# mk.net
KiCad netlist of a schematic drawn in Altium Designer
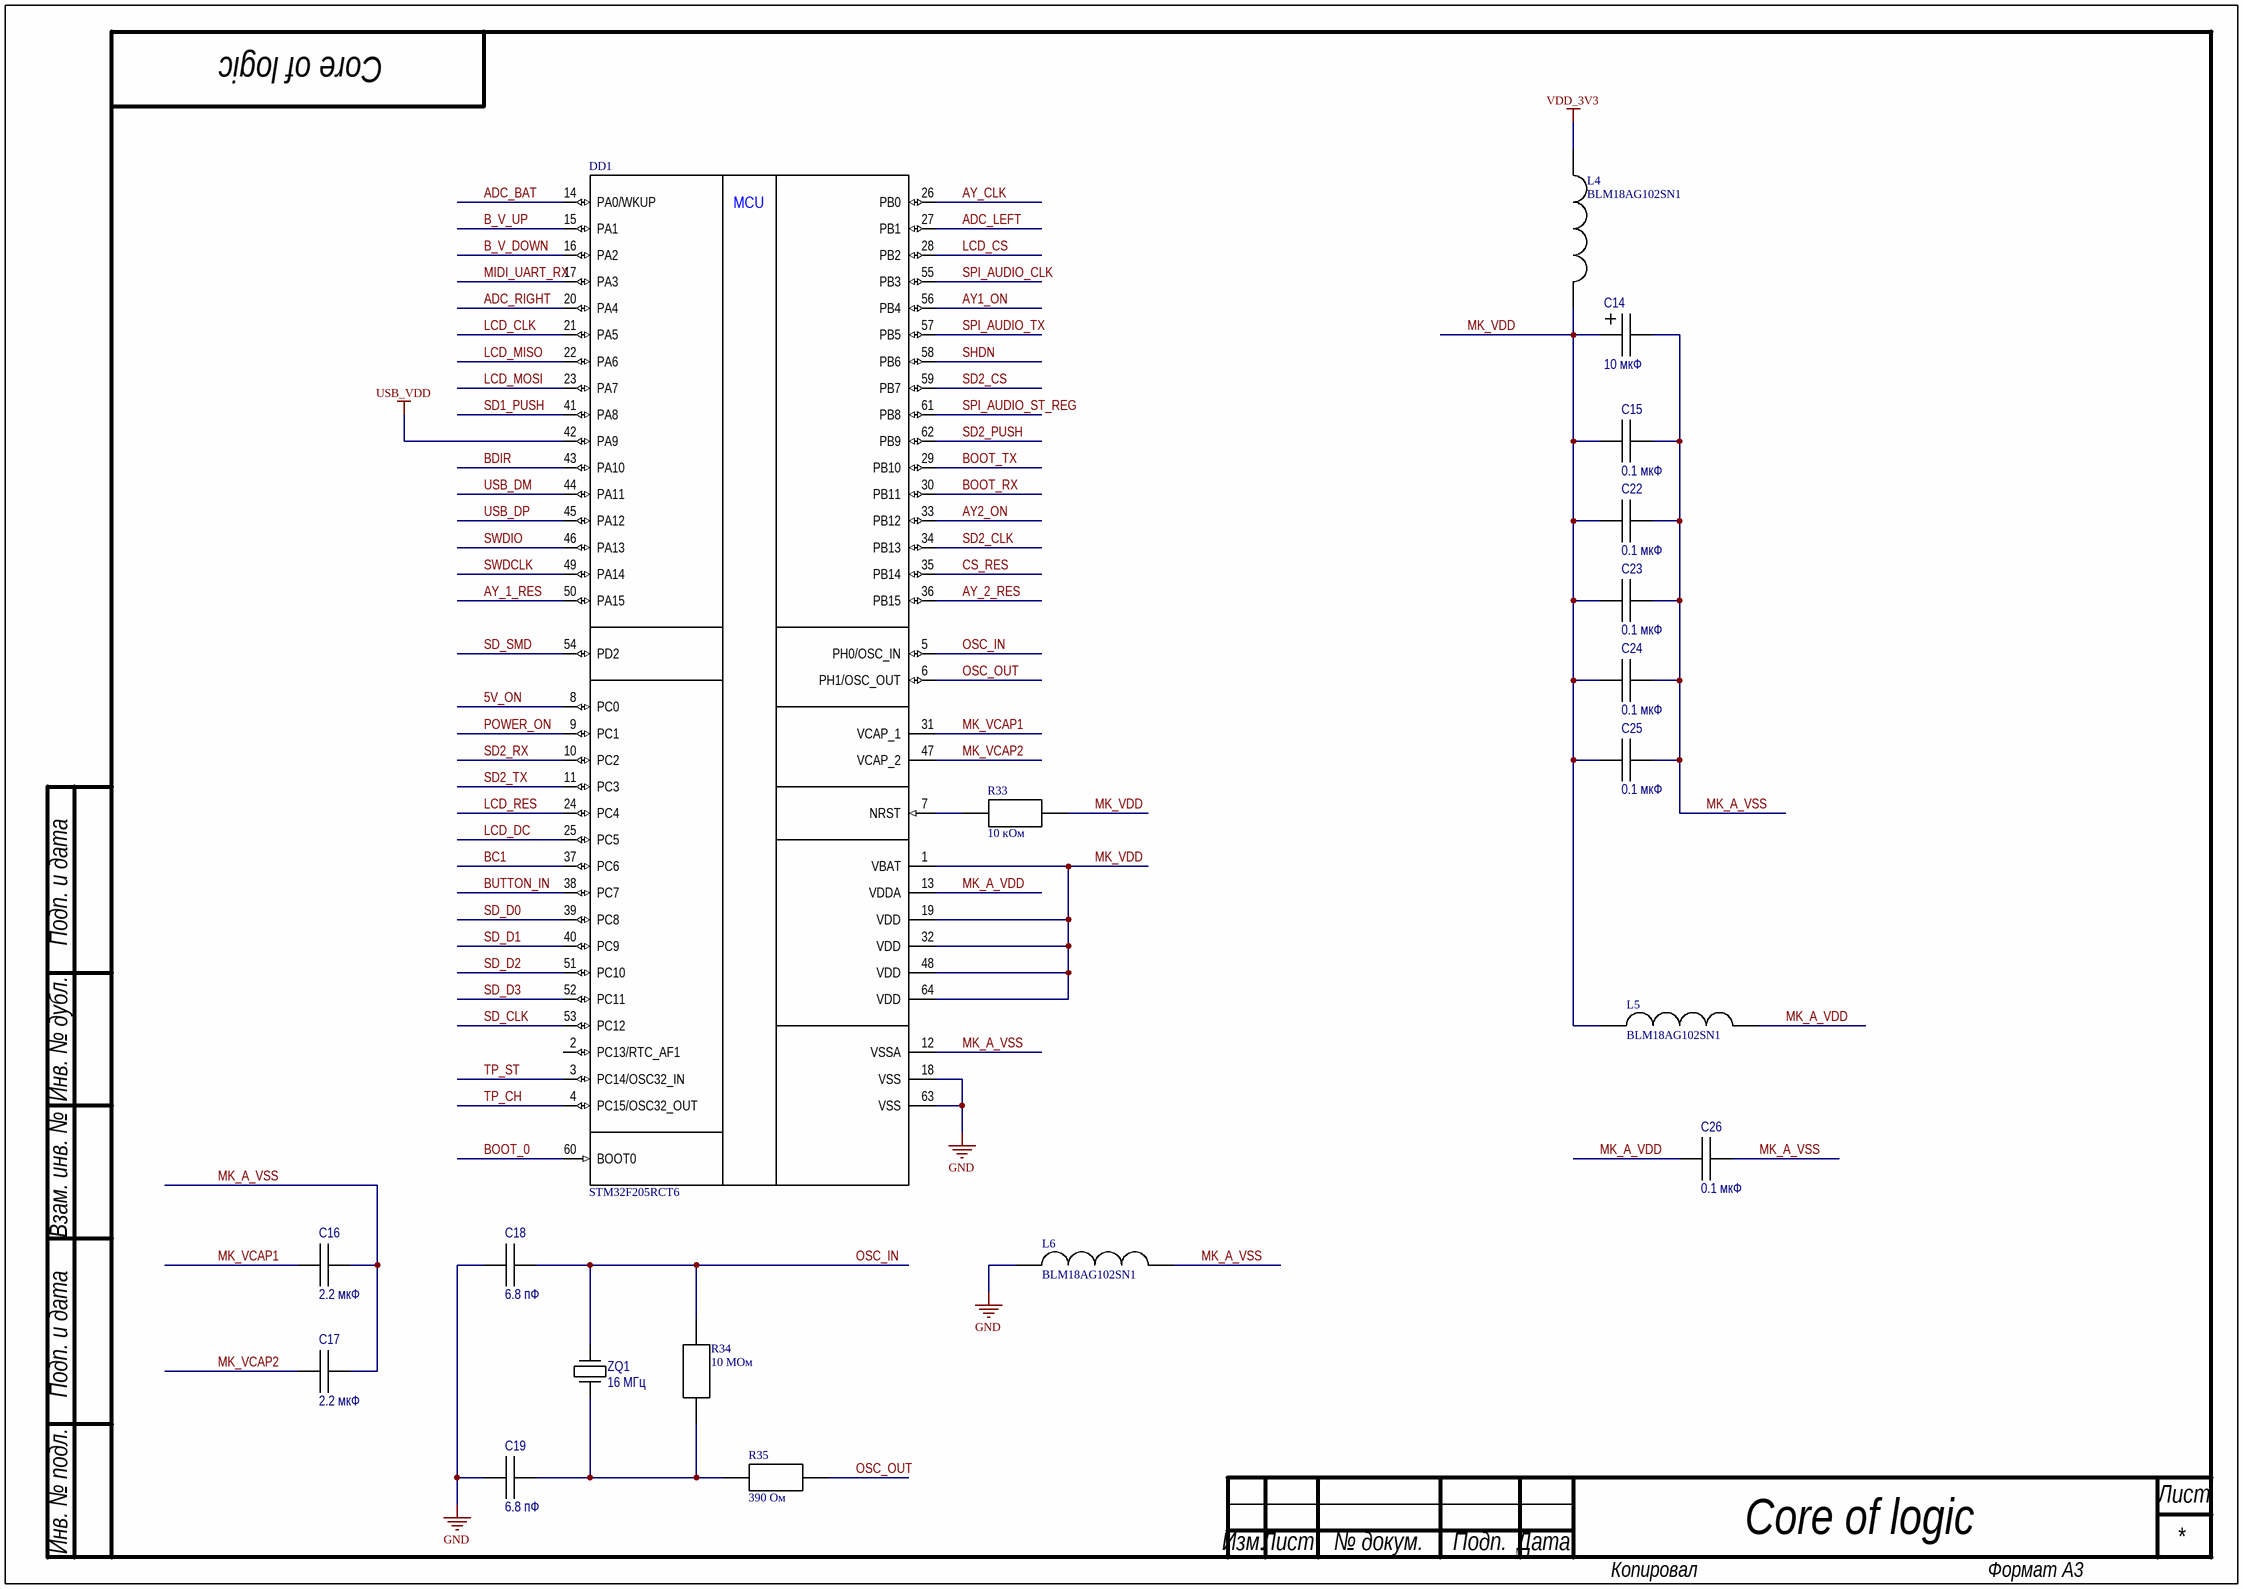
[diagram p0: mk.SchDoc]

(export (version "E")
  (design (tool "Eeschema 10.0.6"))
  (components
    (comp (ref "C14")
      (value "10 мкФ")
      (footprint "C TAN_C")
      (description "SMD Tantalium Capacitor C")
      (fields
        (field (name "TOLERANCE") "/Укажите допуск в процентах/")
        (field (name "MANUFACTURER") "/Укажите компанию-производителя/")
      )
      (libsource (lib "my_lib") (part "CAP TAN_C"))
    )
    (comp (ref "C15")
      (value "0.1 мкФ")
      (footprint "C 1206")
      (description "SMD Capacitor 1206")
      (fields
        (field (name "TOLERANCE") "/Укажите допуск в процентах/")
        (field (name "MANUFACTURER") "/Укажите компанию-производителя/")
      )
      (libsource (lib "my_lib") (part "CAP 1206"))
    )
    (comp (ref "C16")
      (value "2.2 мкФ")
      (footprint "C 1206")
      (description "SMD Capacitor 1206")
      (fields
        (field (name "TOLERANCE") "/Укажите допуск в процентах/")
        (field (name "MANUFACTURER") "/Укажите компанию-производителя/")
      )
      (libsource (lib "my_lib") (part "CAP 1206"))
    )
    (comp (ref "C17")
      (value "2.2 мкФ")
      (footprint "C 1206")
      (description "SMD Capacitor 1206")
      (fields
        (field (name "TOLERANCE") "/Укажите допуск в процентах/")
        (field (name "MANUFACTURER") "/Укажите компанию-производителя/")
      )
      (libsource (lib "my_lib") (part "CAP 1206"))
    )
    (comp (ref "C18")
      (value "6.8 пФ")
      (footprint "C 1206")
      (description "SMD Capacitor 1206")
      (fields
        (field (name "TOLERANCE") "/Укажите допуск в процентах/")
        (field (name "MANUFACTURER") "/Укажите компанию-производителя/")
      )
      (libsource (lib "my_lib") (part "CAP 1206"))
    )
    (comp (ref "C19")
      (value "6.8 пФ")
      (footprint "C 1206")
      (description "SMD Capacitor 1206")
      (fields
        (field (name "TOLERANCE") "/Укажите допуск в процентах/")
        (field (name "MANUFACTURER") "/Укажите компанию-производителя/")
      )
      (libsource (lib "my_lib") (part "CAP 1206"))
    )
    (comp (ref "C22")
      (value "0.1 мкФ")
      (footprint "C 1206")
      (description "SMD Capacitor 1206")
      (fields
        (field (name "TOLERANCE") "/Укажите допуск в процентах/")
        (field (name "MANUFACTURER") "/Укажите компанию-производителя/")
      )
      (libsource (lib "my_lib") (part "CAP 1206"))
    )
    (comp (ref "C23")
      (value "0.1 мкФ")
      (footprint "C 1206")
      (description "SMD Capacitor 1206")
      (fields
        (field (name "TOLERANCE") "/Укажите допуск в процентах/")
        (field (name "MANUFACTURER") "/Укажите компанию-производителя/")
      )
      (libsource (lib "my_lib") (part "CAP 1206"))
    )
    (comp (ref "C24")
      (value "0.1 мкФ")
      (footprint "C 1206")
      (description "SMD Capacitor 1206")
      (fields
        (field (name "TOLERANCE") "/Укажите допуск в процентах/")
        (field (name "MANUFACTURER") "/Укажите компанию-производителя/")
      )
      (libsource (lib "my_lib") (part "CAP 1206"))
    )
    (comp (ref "C25")
      (value "0.1 мкФ")
      (footprint "C 1206")
      (description "SMD Capacitor 1206")
      (fields
        (field (name "TOLERANCE") "/Укажите допуск в процентах/")
        (field (name "MANUFACTURER") "/Укажите компанию-производителя/")
      )
      (libsource (lib "my_lib") (part "CAP 1206"))
    )
    (comp (ref "C26")
      (value "0.1 мкФ")
      (footprint "C 1206")
      (description "SMD Capacitor 1206")
      (fields
        (field (name "TOLERANCE") "/Укажите допуск в процентах/")
        (field (name "MANUFACTURER") "/Укажите компанию-производителя/")
      )
      (libsource (lib "my_lib") (part "CAP 1206"))
    )
    (comp (ref "DD1")
      (value "STM32F205RCT6")
      (footprint "LQFP64")
      (libsource (lib "my_lib") (part "STM32F205RCT6"))
    )
    (comp (ref "L4")
      (value "BLM18AG102SN1")
      (footprint "FB 0603")
      (libsource (lib "my_lib") (part "BLM18AG102SN1"))
    )
    (comp (ref "L5")
      (value "BLM18AG102SN1")
      (footprint "FB 0603")
      (libsource (lib "my_lib") (part "BLM18AG102SN1"))
    )
    (comp (ref "L6")
      (value "BLM18AG102SN1")
      (footprint "FB 0603")
      (libsource (lib "my_lib") (part "BLM18AG102SN1"))
    )
    (comp (ref "R33") (value "10 кОм") (footprint "RES 0805") (libsource (lib "my_lib") (part "RES 0805")))
    (comp (ref "R34") (value "10 МОм") (footprint "RES 0805") (libsource (lib "my_lib") (part "RES 0805")))
    (comp (ref "R35") (value "390 Ом") (footprint "RES 0805") (libsource (lib "my_lib") (part "RES 0805")))
    (comp (ref "ZQ1")
      (value "16 МГц")
      (footprint "NX3225SA")
      (description "QUARTZ CRYSTAL")
      (fields (field (name "MANUFACTURER") "NDK") (field (name "Comment") "NX3225SA-16.000M-STD-CRS-2"))
      (libsource (lib "my_lib") (part "NX3225SA-16.000M-STD-CRS-2"))
    )
  )
  (nets
    (net (code "1") (name "/5V_ON") (class "Default")
      (node (ref "DD1") (pin "8") (pinfunction "PC0_8") (pintype "bidirectional"))
    )
    (net (code "2") (name "/ADC_BAT") (class "Default")
      (node (ref "DD1") (pin "14") (pinfunction "PA0/WKUP_14") (pintype "bidirectional"))
    )
    (net (code "3") (name "/ADC_LEFT") (class "Default")
      (node (ref "DD1") (pin "27") (pinfunction "PB1_27") (pintype "bidirectional"))
    )
    (net (code "4") (name "/ADC_RIGHT") (class "Default")
      (node (ref "DD1") (pin "20") (pinfunction "PA4_20") (pintype "bidirectional"))
    )
    (net (code "5") (name "/AY1_ON") (class "Default")
      (node (ref "DD1") (pin "56") (pinfunction "PB4_56") (pintype "bidirectional"))
    )
    (net (code "6") (name "/AY2_ON") (class "Default")
      (node (ref "DD1") (pin "33") (pinfunction "PB12_33") (pintype "bidirectional"))
    )
    (net (code "7") (name "/AY_1_RES") (class "Default")
      (node (ref "DD1") (pin "50") (pinfunction "PA15_50") (pintype "bidirectional"))
    )
    (net (code "8") (name "/AY_2_RES") (class "Default")
      (node (ref "DD1") (pin "36") (pinfunction "PB15_36") (pintype "bidirectional"))
    )
    (net (code "9") (name "/AY_CLK") (class "Default")
      (node (ref "DD1") (pin "26") (pinfunction "PB0_26") (pintype "bidirectional"))
    )
    (net (code "10") (name "/BC1") (class "Default")
      (node (ref "DD1") (pin "37") (pinfunction "PC6_37") (pintype "bidirectional"))
    )
    (net (code "11") (name "/BDIR") (class "Default")
      (node (ref "DD1") (pin "43") (pinfunction "PA10_43") (pintype "bidirectional"))
    )
    (net (code "12") (name "/BOOT_0") (class "Default")
      (node (ref "DD1") (pin "60") (pinfunction "BOOT0_60") (pintype "input"))
    )
    (net (code "13") (name "/BOOT_RX") (class "Default")
      (node (ref "DD1") (pin "30") (pinfunction "PB11_30") (pintype "bidirectional"))
    )
    (net (code "14") (name "/BOOT_TX") (class "Default")
      (node (ref "DD1") (pin "29") (pinfunction "PB10_29") (pintype "bidirectional"))
    )
    (net (code "15") (name "/BUTTON_IN") (class "Default")
      (node (ref "DD1") (pin "38") (pinfunction "PC7_38") (pintype "bidirectional"))
    )
    (net (code "16") (name "/B_V_DOWN") (class "Default")
      (node (ref "DD1") (pin "16") (pinfunction "PA2_16") (pintype "bidirectional"))
    )
    (net (code "17") (name "/B_V_UP") (class "Default")
      (node (ref "DD1") (pin "15") (pinfunction "PA1_15") (pintype "bidirectional"))
    )
    (net (code "18") (name "/CS_RES") (class "Default")
      (node (ref "DD1") (pin "35") (pinfunction "PB14_35") (pintype "bidirectional"))
    )
    (net (code "19") (name "/LCD_CLK") (class "Default")
      (node (ref "DD1") (pin "21") (pinfunction "PA5_21") (pintype "bidirectional"))
    )
    (net (code "20") (name "/LCD_CS") (class "Default")
      (node (ref "DD1") (pin "28") (pinfunction "PB2_28") (pintype "bidirectional"))
    )
    (net (code "21") (name "/LCD_DC") (class "Default")
      (node (ref "DD1") (pin "25") (pinfunction "PC5_25") (pintype "bidirectional"))
    )
    (net (code "22") (name "/LCD_MISO") (class "Default")
      (node (ref "DD1") (pin "22") (pinfunction "PA6_22") (pintype "bidirectional"))
    )
    (net (code "23") (name "/LCD_MOSI") (class "Default")
      (node (ref "DD1") (pin "23") (pinfunction "PA7_23") (pintype "bidirectional"))
    )
    (net (code "24") (name "/LCD_RES") (class "Default")
      (node (ref "DD1") (pin "24") (pinfunction "PC4_24") (pintype "bidirectional"))
    )
    (net (code "25") (name "/MIDI_UART_RX") (class "Default")
      (node (ref "DD1") (pin "17") (pinfunction "PA3_17") (pintype "bidirectional"))
    )
    (net (code "26") (name "/MK_A_VDD") (class "Default")
      (node (ref "C26") (pin "1") (pinfunction "1_1") (pintype "passive"))
      (node (ref "DD1") (pin "13") (pinfunction "VDDA_13") (pintype "power_in"))
      (node (ref "L5") (pin "2") (pinfunction "2_2") (pintype "passive"))
    )
    (net (code "27") (name "/MK_A_VSS") (class "Default")
      (node (ref "C14") (pin "2") (pinfunction "2_2") (pintype "passive"))
      (node (ref "C15") (pin "2") (pinfunction "2_2") (pintype "passive"))
      (node (ref "C16") (pin "2") (pinfunction "2_2") (pintype "passive"))
      (node (ref "C17") (pin "2") (pinfunction "2_2") (pintype "passive"))
      (node (ref "C22") (pin "2") (pinfunction "2_2") (pintype "passive"))
      (node (ref "C23") (pin "2") (pinfunction "2_2") (pintype "passive"))
      (node (ref "C24") (pin "2") (pinfunction "2_2") (pintype "passive"))
      (node (ref "C25") (pin "2") (pinfunction "2_2") (pintype "passive"))
      (node (ref "C26") (pin "2") (pinfunction "2_2") (pintype "passive"))
      (node (ref "DD1") (pin "12") (pinfunction "VSSA_12") (pintype "power_in"))
      (node (ref "L6") (pin "2") (pinfunction "2_2") (pintype "passive"))
    )
    (net (code "28") (name "/MK_VCAP1") (class "Default")
      (node (ref "C16") (pin "1") (pinfunction "1_1") (pintype "passive"))
      (node (ref "DD1") (pin "31") (pinfunction "VCAP_1_31") (pintype "power_in"))
    )
    (net (code "29") (name "/MK_VCAP2") (class "Default")
      (node (ref "C17") (pin "1") (pinfunction "1_1") (pintype "passive"))
      (node (ref "DD1") (pin "47") (pinfunction "VCAP_2_47") (pintype "power_in"))
    )
    (net (code "30") (name "/MK_VDD") (class "Default")
      (node (ref "C14") (pin "1") (pinfunction "1_1") (pintype "passive"))
      (node (ref "C15") (pin "1") (pinfunction "1_1") (pintype "passive"))
      (node (ref "C22") (pin "1") (pinfunction "1_1") (pintype "passive"))
      (node (ref "C23") (pin "1") (pinfunction "1_1") (pintype "passive"))
      (node (ref "C24") (pin "1") (pinfunction "1_1") (pintype "passive"))
      (node (ref "C25") (pin "1") (pinfunction "1_1") (pintype "passive"))
      (node (ref "DD1") (pin "1") (pinfunction "VBAT_1") (pintype "power_in"))
      (node (ref "DD1") (pin "19") (pinfunction "VDD_19") (pintype "power_in"))
      (node (ref "DD1") (pin "32") (pinfunction "VDD_32") (pintype "power_in"))
      (node (ref "DD1") (pin "48") (pinfunction "VDD_48") (pintype "power_in"))
      (node (ref "DD1") (pin "64") (pinfunction "VDD_64") (pintype "power_in"))
      (node (ref "L4") (pin "2") (pinfunction "2_2") (pintype "passive"))
      (node (ref "L5") (pin "1") (pinfunction "1_1") (pintype "passive"))
      (node (ref "R33") (pin "2") (pinfunction "2_2") (pintype "passive"))
    )
    (net (code "31") (name "/OSC_IN") (class "Default")
      (node (ref "C18") (pin "2") (pinfunction "2_2") (pintype "passive"))
      (node (ref "DD1") (pin "5") (pinfunction "PH0/OSC_IN_5") (pintype "bidirectional"))
      (node (ref "R34") (pin "2") (pinfunction "2_2") (pintype "passive"))
      (node (ref "ZQ1") (pin "3") (pinfunction "XO_3") (pintype "passive"))
    )
    (net (code "32") (name "/OSC_OUT") (class "Default")
      (node (ref "DD1") (pin "6") (pinfunction "PH1/OSC_OUT_6") (pintype "bidirectional"))
      (node (ref "R35") (pin "2") (pinfunction "2_2") (pintype "passive"))
    )
    (net (code "33") (name "/POWER_ON") (class "Default")
      (node (ref "DD1") (pin "9") (pinfunction "PC1_9") (pintype "bidirectional"))
    )
    (net (code "34") (name "/SD1_PUSH") (class "Default")
      (node (ref "DD1") (pin "41") (pinfunction "PA8_41") (pintype "bidirectional"))
    )
    (net (code "35") (name "/SD2_CLK") (class "Default")
      (node (ref "DD1") (pin "34") (pinfunction "PB13_34") (pintype "bidirectional"))
    )
    (net (code "36") (name "/SD2_CS") (class "Default")
      (node (ref "DD1") (pin "59") (pinfunction "PB7_59") (pintype "bidirectional"))
    )
    (net (code "37") (name "/SD2_PUSH") (class "Default")
      (node (ref "DD1") (pin "62") (pinfunction "PB9_62") (pintype "bidirectional"))
    )
    (net (code "38") (name "/SD2_RX") (class "Default")
      (node (ref "DD1") (pin "10") (pinfunction "PC2_10") (pintype "bidirectional"))
    )
    (net (code "39") (name "/SD2_TX") (class "Default")
      (node (ref "DD1") (pin "11") (pinfunction "PC3_11") (pintype "bidirectional"))
    )
    (net (code "40") (name "/SD_CLK") (class "Default")
      (node (ref "DD1") (pin "53") (pinfunction "PC12_53") (pintype "bidirectional"))
    )
    (net (code "41") (name "/SD_D0") (class "Default")
      (node (ref "DD1") (pin "39") (pinfunction "PC8_39") (pintype "bidirectional"))
    )
    (net (code "42") (name "/SD_D1") (class "Default")
      (node (ref "DD1") (pin "40") (pinfunction "PC9_40") (pintype "bidirectional"))
    )
    (net (code "43") (name "/SD_D2") (class "Default")
      (node (ref "DD1") (pin "51") (pinfunction "PC10_51") (pintype "bidirectional"))
    )
    (net (code "44") (name "/SD_D3") (class "Default")
      (node (ref "DD1") (pin "52") (pinfunction "PC11_52") (pintype "bidirectional"))
    )
    (net (code "45") (name "/SD_SMD") (class "Default")
      (node (ref "DD1") (pin "54") (pinfunction "PD2_54") (pintype "bidirectional"))
    )
    (net (code "46") (name "/SHDN") (class "Default")
      (node (ref "DD1") (pin "58") (pinfunction "PB6_58") (pintype "bidirectional"))
    )
    (net (code "47") (name "/SPI_AUDIO_CLK") (class "Default")
      (node (ref "DD1") (pin "55") (pinfunction "PB3_55") (pintype "bidirectional"))
    )
    (net (code "48") (name "/SPI_AUDIO_ST_REG") (class "Default")
      (node (ref "DD1") (pin "61") (pinfunction "PB8_61") (pintype "bidirectional"))
    )
    (net (code "49") (name "/SPI_AUDIO_TX") (class "Default")
      (node (ref "DD1") (pin "57") (pinfunction "PB5_57") (pintype "bidirectional"))
    )
    (net (code "50") (name "/SWDCLK") (class "Default")
      (node (ref "DD1") (pin "49") (pinfunction "PA14_49") (pintype "bidirectional"))
    )
    (net (code "51") (name "/SWDIO") (class "Default")
      (node (ref "DD1") (pin "46") (pinfunction "PA13_46") (pintype "bidirectional"))
    )
    (net (code "52") (name "/TP_CH") (class "Default")
      (node (ref "DD1") (pin "4") (pinfunction "PC15/OSC32_OUT_4") (pintype "bidirectional"))
    )
    (net (code "53") (name "/TP_ST") (class "Default")
      (node (ref "DD1") (pin "3") (pinfunction "PC14/OSC32_IN_3") (pintype "bidirectional"))
    )
    (net (code "54") (name "/USB_DM") (class "Default")
      (node (ref "DD1") (pin "44") (pinfunction "PA11_44") (pintype "bidirectional"))
    )
    (net (code "55") (name "/USB_DP") (class "Default")
      (node (ref "DD1") (pin "45") (pinfunction "PA12_45") (pintype "bidirectional"))
    )
    (net (code "56") (name "GND") (class "Default")
      (node (ref "C18") (pin "1") (pinfunction "1_1") (pintype "passive"))
      (node (ref "C19") (pin "1") (pinfunction "1_1") (pintype "passive"))
      (node (ref "DD1") (pin "18") (pinfunction "VSS_18") (pintype "power_in"))
      (node (ref "DD1") (pin "63") (pinfunction "VSS_63") (pintype "power_in"))
      (node (ref "L6") (pin "1") (pinfunction "1_1") (pintype "passive"))
    )
    (net (code "57") (name "Net-(DD1-NRST)") (class "Default")
      (node (ref "DD1") (pin "7") (pinfunction "NRST_7") (pintype "input"))
      (node (ref "R33") (pin "1") (pinfunction "1_1") (pintype "passive"))
    )
    (net (code "58") (name "Net-(ZQ1-XI)") (class "Default")
      (node (ref "C19") (pin "2") (pinfunction "2_2") (pintype "passive"))
      (node (ref "R34") (pin "1") (pinfunction "1_1") (pintype "passive"))
      (node (ref "R35") (pin "1") (pinfunction "1_1") (pintype "passive"))
      (node (ref "ZQ1") (pin "1") (pinfunction "XI_1") (pintype "passive"))
    )
    (net (code "59") (name "USB_VDD") (class "Default")
      (node (ref "DD1") (pin "42") (pinfunction "PA9_42") (pintype "bidirectional"))
    )
    (net (code "60") (name "VDD_3V3") (class "Default")
      (node (ref "L4") (pin "1") (pinfunction "1_1") (pintype "passive"))
    )
    (net (code "61") (name "unconnected-(DD1-PC13{slash}RTC_AF1-Pad2)") (class "Default")
      (node (ref "DD1") (pin "2") (pinfunction "PC13/RTC_AF1_2") (pintype "bidirectional"))
    )
    (net (code "62") (name "unconnected-(ZQ1-NC-Pad2)") (class "Default")
      (node (ref "ZQ1") (pin "2") (pinfunction "NC_2") (pintype "passive"))
    )
    (net (code "63") (name "unconnected-(ZQ1-NC-Pad4)") (class "Default")
      (node (ref "ZQ1") (pin "4") (pinfunction "NC_4") (pintype "passive"))
    )
  )
)
